# AD.net
KiCad netlist of a schematic drawn in Altium Designer
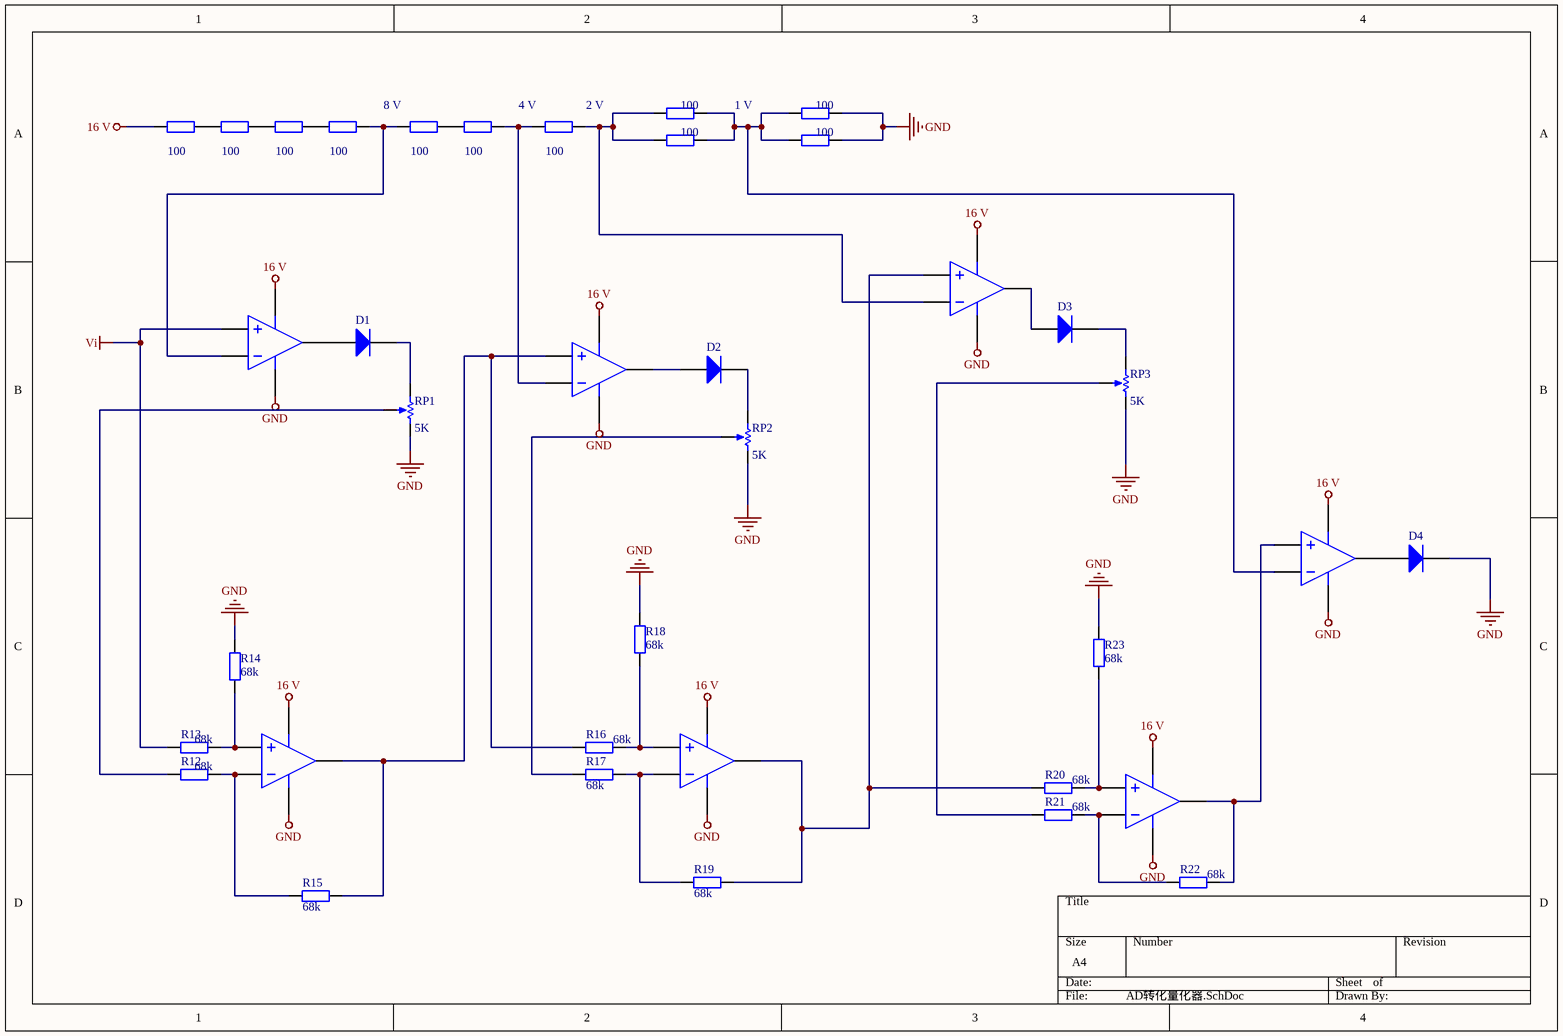
[diagram p0: AD转化量化器.SchDoc]

(export (version "E")
  (design (tool "Eeschema 10.0.6"))
  (components
    (comp (ref "D1")
      (value "Diode 1N914")
      (footprint "DO-35")
      (description "High Conductance Fast Diode")
      (fields (field (name "PUBLISHER") "Altium Limited"))
      (libsource (lib "Miscellaneous Devices") (part "Diode 1N914"))
    )
    (comp (ref "D2")
      (value "Diode 1N914")
      (footprint "DO-35")
      (description "High Conductance Fast Diode")
      (fields (field (name "PUBLISHER") "Altium Limited"))
      (libsource (lib "Miscellaneous Devices") (part "Diode 1N914"))
    )
    (comp (ref "D3")
      (value "Diode 1N914")
      (footprint "DO-35")
      (description "High Conductance Fast Diode")
      (fields (field (name "PUBLISHER") "Altium Limited"))
      (libsource (lib "Miscellaneous Devices") (part "Diode 1N914"))
    )
    (comp (ref "D4")
      (value "Diode 1N914")
      (footprint "DO-35")
      (description "High Conductance Fast Diode")
      (fields (field (name "PUBLISHER") "Altium Limited"))
      (libsource (lib "Miscellaneous Devices") (part "Diode 1N914"))
    )
    (comp (ref "R1")
      (value "100")
      (footprint "AXIAL-0.4")
      (description "Resistor")
      (fields (field (name "Comment") "Res2") (field (name "PUBLISHER") "Altium Limited"))
      (libsource (lib "Miscellaneous Devices") (part "Res2"))
    )
    (comp (ref "R2")
      (value "100")
      (footprint "AXIAL-0.4")
      (description "Resistor")
      (fields (field (name "Comment") "Res2") (field (name "PUBLISHER") "Altium Limited"))
      (libsource (lib "Miscellaneous Devices") (part "Res2"))
    )
    (comp (ref "R3")
      (value "100")
      (footprint "AXIAL-0.4")
      (description "Resistor")
      (fields (field (name "Comment") "Res2") (field (name "PUBLISHER") "Altium Limited"))
      (libsource (lib "Miscellaneous Devices") (part "Res2"))
    )
    (comp (ref "R4")
      (value "100")
      (footprint "AXIAL-0.4")
      (description "Resistor")
      (fields (field (name "Comment") "Res2") (field (name "PUBLISHER") "Altium Limited"))
      (libsource (lib "Miscellaneous Devices") (part "Res2"))
    )
    (comp (ref "R5")
      (value "100")
      (footprint "AXIAL-0.4")
      (description "Resistor")
      (fields (field (name "Comment") "Res2") (field (name "PUBLISHER") "Altium Limited"))
      (libsource (lib "Miscellaneous Devices") (part "Res2"))
    )
    (comp (ref "R6")
      (value "100")
      (footprint "AXIAL-0.4")
      (description "Resistor")
      (fields (field (name "Comment") "Res2") (field (name "PUBLISHER") "Altium Limited"))
      (libsource (lib "Miscellaneous Devices") (part "Res2"))
    )
    (comp (ref "R7")
      (value "100")
      (footprint "AXIAL-0.4")
      (description "Resistor")
      (fields (field (name "Comment") "Res2") (field (name "PUBLISHER") "Altium Limited"))
      (libsource (lib "Miscellaneous Devices") (part "Res2"))
    )
    (comp (ref "R8")
      (value "100")
      (footprint "AXIAL-0.4")
      (description "Resistor")
      (fields (field (name "Comment") "Res2") (field (name "PUBLISHER") "Altium Limited"))
      (libsource (lib "Miscellaneous Devices") (part "Res2"))
    )
    (comp (ref "R9")
      (value "100")
      (footprint "AXIAL-0.4")
      (description "Resistor")
      (fields (field (name "Comment") "Res2") (field (name "PUBLISHER") "Altium Limited"))
      (libsource (lib "Miscellaneous Devices") (part "Res2"))
    )
    (comp (ref "R10")
      (value "100")
      (footprint "AXIAL-0.4")
      (description "Resistor")
      (fields (field (name "Comment") "Res2") (field (name "PUBLISHER") "Altium Limited"))
      (libsource (lib "Miscellaneous Devices") (part "Res2"))
    )
    (comp (ref "R11")
      (value "100")
      (footprint "AXIAL-0.4")
      (description "Resistor")
      (fields (field (name "Comment") "Res2") (field (name "PUBLISHER") "Altium Limited"))
      (libsource (lib "Miscellaneous Devices") (part "Res2"))
    )
    (comp (ref "R12")
      (value "68k")
      (footprint "AXIAL-0.4")
      (description "Resistor")
      (fields (field (name "Comment") "Res2") (field (name "PUBLISHER") "Altium Limited"))
      (libsource (lib "Miscellaneous Devices") (part "Res2"))
    )
    (comp (ref "R13")
      (value "68k")
      (footprint "AXIAL-0.4")
      (description "Resistor")
      (fields (field (name "Comment") "Res2") (field (name "PUBLISHER") "Altium Limited"))
      (libsource (lib "Miscellaneous Devices") (part "Res2"))
    )
    (comp (ref "R14")
      (value "68k")
      (footprint "AXIAL-0.4")
      (description "Resistor")
      (fields (field (name "Comment") "Res2") (field (name "PUBLISHER") "Altium Limited"))
      (libsource (lib "") (part "Res2_2"))
    )
    (comp (ref "R15")
      (value "68k")
      (footprint "AXIAL-0.4")
      (description "Resistor")
      (fields (field (name "Comment") "Res2") (field (name "PUBLISHER") "Altium Limited"))
      (libsource (lib "") (part "Res2_1"))
    )
    (comp (ref "R16")
      (value "68k")
      (footprint "AXIAL-0.4")
      (description "Resistor")
      (fields (field (name "Comment") "Res2") (field (name "PUBLISHER") "Altium Limited"))
      (libsource (lib "") (part "Res2_1"))
    )
    (comp (ref "R17")
      (value "68k")
      (footprint "AXIAL-0.4")
      (description "Resistor")
      (fields (field (name "Comment") "Res2") (field (name "PUBLISHER") "Altium Limited"))
      (libsource (lib "") (part "Res2_1"))
    )
    (comp (ref "R18")
      (value "68k")
      (footprint "AXIAL-0.4")
      (description "Resistor")
      (fields (field (name "Comment") "Res2") (field (name "PUBLISHER") "Altium Limited"))
      (libsource (lib "") (part "Res2_3"))
    )
    (comp (ref "R19")
      (value "68k")
      (footprint "AXIAL-0.4")
      (description "Resistor")
      (fields (field (name "Comment") "Res2") (field (name "PUBLISHER") "Altium Limited"))
      (libsource (lib "Miscellaneous Devices") (part "Res2"))
    )
    (comp (ref "R20")
      (value "68k")
      (footprint "AXIAL-0.4")
      (description "Resistor")
      (fields (field (name "Comment") "Res2") (field (name "PUBLISHER") "Altium Limited"))
      (libsource (lib "Miscellaneous Devices") (part "Res2"))
    )
    (comp (ref "R21")
      (value "68k")
      (footprint "AXIAL-0.4")
      (description "Resistor")
      (fields (field (name "Comment") "Res2") (field (name "PUBLISHER") "Altium Limited"))
      (libsource (lib "Miscellaneous Devices") (part "Res2"))
    )
    (comp (ref "R22")
      (value "68k")
      (footprint "AXIAL-0.4")
      (description "Resistor")
      (fields (field (name "Comment") "Res2") (field (name "PUBLISHER") "Altium Limited"))
      (libsource (lib "Miscellaneous Devices") (part "Res2"))
    )
    (comp (ref "R23")
      (value "68k")
      (footprint "AXIAL-0.4")
      (description "Resistor")
      (fields (field (name "Comment") "Res2") (field (name "PUBLISHER") "Altium Limited"))
      (libsource (lib "") (part "Res2_2"))
    )
    (comp (ref "RP1")
      (value "5K")
      (footprint "VR5")
      (description "Potentiometer")
      (fields (field (name "Comment") "RPot") (field (name "PUBLISHER") "Altium Limited"))
      (libsource (lib "Miscellaneous Devices") (part "RPot"))
    )
    (comp (ref "RP2")
      (value "5K")
      (footprint "VR5")
      (description "Potentiometer")
      (fields (field (name "Comment") "RPot") (field (name "PUBLISHER") "Altium Limited"))
      (libsource (lib "Miscellaneous Devices") (part "RPot"))
    )
    (comp (ref "RP3")
      (value "5K")
      (footprint "VR5")
      (description "Potentiometer")
      (fields (field (name "Comment") "RPot") (field (name "PUBLISHER") "Altium Limited"))
      (libsource (lib "Miscellaneous Devices") (part "RPot"))
    )
    (comp (ref "U1")
      (value "LM324AN")
      (footprint "N14A")
      (description "Low Power Quad Operational Amplifier, 14-pin MDIP")
      (fields
        (field (name "MANUFACTURER") "National Semiconductor")
        (field (name "PUBLISHER") "Altium Limited")
      )
      (libsource (lib "NSC Amplifier") (part "LM324AN"))
    )
    (comp (ref "U2")
      (value "LM324AN")
      (footprint "N14A")
      (description "Low Power Quad Operational Amplifier, 14-pin MDIP")
      (fields
        (field (name "MANUFACTURER") "National Semiconductor")
        (field (name "PUBLISHER") "Altium Limited")
      )
      (libsource (lib "NSC Amplifier") (part "LM324AN"))
    )
  )
  (nets
    (net (code "1") (name "16 V") (class "Default")
      (node (ref "R1") (pin "1") (pinfunction "1_1") (pintype "passive"))
      (node (ref "U1") (pin "11") (pinfunction "GND_11") (pintype "power_in"))
      (node (ref "U2") (pin "11") (pinfunction "GND_11") (pintype "power_in"))
    )
    (net (code "2") (name "GND") (class "Default")
      (node (ref "D4") (pin "2") (pinfunction "K_2") (pintype "passive"))
      (node (ref "R10") (pin "2") (pinfunction "2_2") (pintype "passive"))
      (node (ref "R11") (pin "2") (pinfunction "2_2") (pintype "passive"))
      (node (ref "R14") (pin "2") (pinfunction "2_2") (pintype "passive"))
      (node (ref "R18") (pin "1") (pinfunction "1_1") (pintype "passive"))
      (node (ref "R23") (pin "2") (pinfunction "2_2") (pintype "passive"))
      (node (ref "RP1") (pin "2") (pinfunction "BOT_2") (pintype "passive"))
      (node (ref "RP2") (pin "2") (pinfunction "BOT_2") (pintype "passive"))
      (node (ref "RP3") (pin "2") (pinfunction "BOT_2") (pintype "passive"))
      (node (ref "U1") (pin "4") (pinfunction "V+_4") (pintype "power_in"))
      (node (ref "U2") (pin "4") (pinfunction "V+_4") (pintype "power_in"))
    )
    (net (code "3") (name "Net-(D1-A)") (class "Default")
      (node (ref "D1") (pin "1") (pinfunction "A_1") (pintype "passive"))
      (node (ref "U1") (pin "1") (pinfunction "OUT1_1") (pintype "output"))
    )
    (net (code "4") (name "Net-(D1-K)") (class "Default")
      (node (ref "D1") (pin "2") (pinfunction "K_2") (pintype "passive"))
      (node (ref "RP1") (pin "1") (pinfunction "TOP_1") (pintype "passive"))
    )
    (net (code "5") (name "Net-(D2-A)") (class "Default")
      (node (ref "D2") (pin "1") (pinfunction "A_1") (pintype "passive"))
      (node (ref "U1") (pin "14") (pinfunction "OUT4_14") (pintype "output"))
    )
    (net (code "6") (name "Net-(D2-K)") (class "Default")
      (node (ref "D2") (pin "2") (pinfunction "K_2") (pintype "passive"))
      (node (ref "RP2") (pin "1") (pinfunction "TOP_1") (pintype "passive"))
    )
    (net (code "7") (name "Net-(D3-A)") (class "Default")
      (node (ref "D3") (pin "1") (pinfunction "A_1") (pintype "passive"))
      (node (ref "U2") (pin "1") (pinfunction "OUT1_1") (pintype "output"))
    )
    (net (code "8") (name "Net-(D3-K)") (class "Default")
      (node (ref "D3") (pin "2") (pinfunction "K_2") (pintype "passive"))
      (node (ref "RP3") (pin "1") (pinfunction "TOP_1") (pintype "passive"))
    )
    (net (code "9") (name "Net-(D4-A)") (class "Default")
      (node (ref "D4") (pin "1") (pinfunction "A_1") (pintype "passive"))
      (node (ref "U2") (pin "14") (pinfunction "OUT4_14") (pintype "output"))
    )
    (net (code "10") (name "Net-(R1-Pad2)") (class "Default")
      (node (ref "R1") (pin "2") (pinfunction "2_2") (pintype "passive"))
      (node (ref "R2") (pin "1") (pinfunction "1_1") (pintype "passive"))
    )
    (net (code "11") (name "Net-(R2-Pad2)") (class "Default")
      (node (ref "R2") (pin "2") (pinfunction "2_2") (pintype "passive"))
      (node (ref "R3") (pin "1") (pinfunction "1_1") (pintype "passive"))
    )
    (net (code "12") (name "Net-(R3-Pad2)") (class "Default")
      (node (ref "R3") (pin "2") (pinfunction "2_2") (pintype "passive"))
      (node (ref "R4") (pin "1") (pinfunction "1_1") (pintype "passive"))
    )
    (net (code "13") (name "Net-(R5-Pad2)") (class "Default")
      (node (ref "R5") (pin "2") (pinfunction "2_2") (pintype "passive"))
      (node (ref "R6") (pin "1") (pinfunction "1_1") (pintype "passive"))
    )
    (net (code "14") (name "Net-(RP1-TAP)") (class "Default")
      (node (ref "R12") (pin "1") (pinfunction "1_1") (pintype "passive"))
      (node (ref "RP1") (pin "3") (pinfunction "TAP_3") (pintype "passive"))
    )
    (net (code "15") (name "Net-(RP2-TAP)") (class "Default")
      (node (ref "R17") (pin "2") (pinfunction "2_2") (pintype "passive"))
      (node (ref "RP2") (pin "3") (pinfunction "TAP_3") (pintype "passive"))
    )
    (net (code "16") (name "Net-(RP3-TAP)") (class "Default")
      (node (ref "R21") (pin "1") (pinfunction "1_1") (pintype "passive"))
      (node (ref "RP3") (pin "3") (pinfunction "TAP_3") (pintype "passive"))
    )
    (net (code "17") (name "Net-(U1A-IN1-)") (class "Default")
      (node (ref "R4") (pin "2") (pinfunction "2_2") (pintype "passive"))
      (node (ref "R5") (pin "1") (pinfunction "1_1") (pintype "passive"))
      (node (ref "U1") (pin "2") (pinfunction "IN1-_2") (pintype "input"))
    )
    (net (code "18") (name "Net-(U1B-IN2+)") (class "Default")
      (node (ref "R13") (pin "2") (pinfunction "2_2") (pintype "passive"))
      (node (ref "R14") (pin "1") (pinfunction "1_1") (pintype "passive"))
      (node (ref "U1") (pin "5") (pinfunction "IN2+_5") (pintype "input"))
    )
    (net (code "19") (name "Net-(U1B-IN2-)") (class "Default")
      (node (ref "R12") (pin "2") (pinfunction "2_2") (pintype "passive"))
      (node (ref "R15") (pin "2") (pinfunction "2_2") (pintype "passive"))
      (node (ref "U1") (pin "6") (pinfunction "IN2-_6") (pintype "input"))
    )
    (net (code "20") (name "Net-(U1B-OUT2)") (class "Default")
      (node (ref "R15") (pin "1") (pinfunction "1_1") (pintype "passive"))
      (node (ref "R16") (pin "2") (pinfunction "2_2") (pintype "passive"))
      (node (ref "U1") (pin "12") (pinfunction "IN4+_12") (pintype "input"))
      (node (ref "U1") (pin "7") (pinfunction "OUT2_7") (pintype "output"))
    )
    (net (code "21") (name "Net-(U1C-IN3+)") (class "Default")
      (node (ref "R16") (pin "1") (pinfunction "1_1") (pintype "passive"))
      (node (ref "R18") (pin "2") (pinfunction "2_2") (pintype "passive"))
      (node (ref "U1") (pin "10") (pinfunction "IN3+_10") (pintype "passive"))
    )
    (net (code "22") (name "Net-(U1C-IN3-)") (class "Default")
      (node (ref "R17") (pin "1") (pinfunction "1_1") (pintype "passive"))
      (node (ref "R19") (pin "1") (pinfunction "1_1") (pintype "passive"))
      (node (ref "U1") (pin "9") (pinfunction "IN3-_9") (pintype "passive"))
    )
    (net (code "23") (name "Net-(U1C-OUT3)") (class "Default")
      (node (ref "R19") (pin "2") (pinfunction "2_2") (pintype "passive"))
      (node (ref "R20") (pin "1") (pinfunction "1_1") (pintype "passive"))
      (node (ref "U1") (pin "8") (pinfunction "OUT3_8") (pintype "passive"))
      (node (ref "U2") (pin "3") (pinfunction "IN1+_3") (pintype "input"))
    )
    (net (code "24") (name "Net-(U1D-IN4-)") (class "Default")
      (node (ref "R6") (pin "2") (pinfunction "2_2") (pintype "passive"))
      (node (ref "R7") (pin "1") (pinfunction "1_1") (pintype "passive"))
      (node (ref "U1") (pin "13") (pinfunction "IN4-_13") (pintype "input"))
    )
    (net (code "25") (name "Net-(U2A-IN1-)") (class "Default")
      (node (ref "R7") (pin "2") (pinfunction "2_2") (pintype "passive"))
      (node (ref "R8") (pin "1") (pinfunction "1_1") (pintype "passive"))
      (node (ref "R9") (pin "1") (pinfunction "1_1") (pintype "passive"))
      (node (ref "U2") (pin "2") (pinfunction "IN1-_2") (pintype "input"))
    )
    (net (code "26") (name "Net-(U2B-IN2+)") (class "Default")
      (node (ref "R20") (pin "2") (pinfunction "2_2") (pintype "passive"))
      (node (ref "R23") (pin "1") (pinfunction "1_1") (pintype "passive"))
      (node (ref "U2") (pin "5") (pinfunction "IN2+_5") (pintype "input"))
    )
    (net (code "27") (name "Net-(U2B-IN2-)") (class "Default")
      (node (ref "R21") (pin "2") (pinfunction "2_2") (pintype "passive"))
      (node (ref "R22") (pin "1") (pinfunction "1_1") (pintype "passive"))
      (node (ref "U2") (pin "6") (pinfunction "IN2-_6") (pintype "input"))
    )
    (net (code "28") (name "Net-(U2B-OUT2)") (class "Default")
      (node (ref "R22") (pin "2") (pinfunction "2_2") (pintype "passive"))
      (node (ref "U2") (pin "12") (pinfunction "IN4+_12") (pintype "input"))
      (node (ref "U2") (pin "7") (pinfunction "OUT2_7") (pintype "output"))
    )
    (net (code "29") (name "Net-(U2D-IN4-)") (class "Default")
      (node (ref "R10") (pin "1") (pinfunction "1_1") (pintype "passive"))
      (node (ref "R11") (pin "1") (pinfunction "1_1") (pintype "passive"))
      (node (ref "R8") (pin "2") (pinfunction "2_2") (pintype "passive"))
      (node (ref "R9") (pin "2") (pinfunction "2_2") (pintype "passive"))
      (node (ref "U2") (pin "13") (pinfunction "IN4-_13") (pintype "input"))
    )
    (net (code "30") (name "Vi") (class "Default")
      (node (ref "R13") (pin "1") (pinfunction "1_1") (pintype "passive"))
      (node (ref "U1") (pin "3") (pinfunction "IN1+_3") (pintype "input"))
    )
  )
)
